# Single-Phase-Energy-Meter_v1_4-rev1.net
KiCad netlist of a schematic drawn in EAGLE
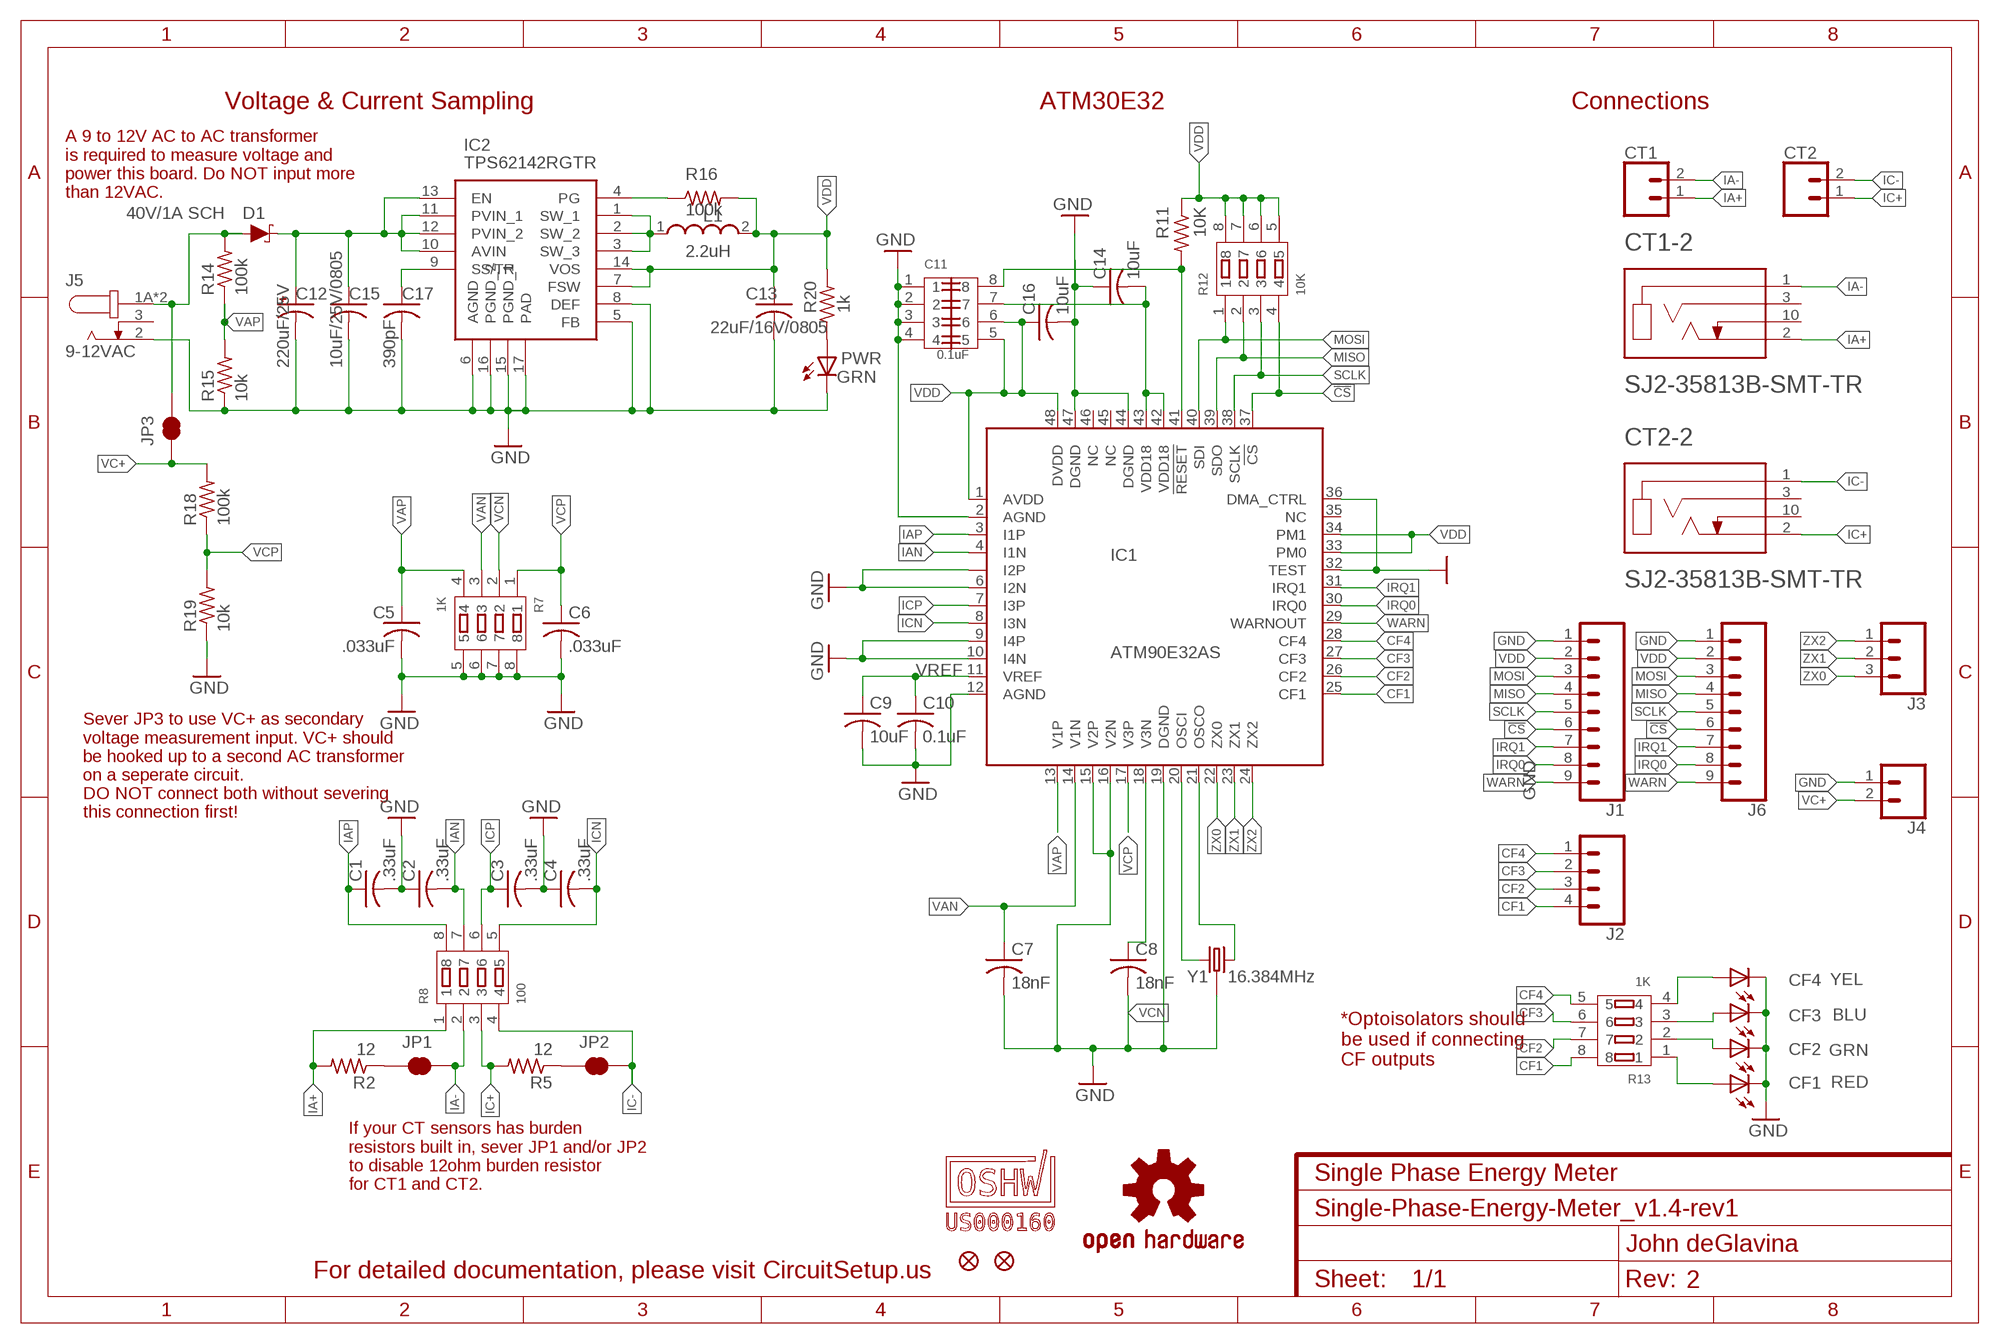
[diagram p0: schematic, sheet 1]

(export (version "E")
  (design (tool "Eeschema 10.0.6"))
  (components
    (comp (ref "C1")
      (value ".33uF")
      (footprint "eagle-import:C0603")
      (libsource (lib "eagle-import") (part "C-USC0603"))
    )
    (comp (ref "C2")
      (value ".33uF")
      (footprint "eagle-import:C0603")
      (libsource (lib "eagle-import") (part "C-USC0603"))
    )
    (comp (ref "C3")
      (value ".33uF")
      (footprint "eagle-import:C0603")
      (libsource (lib "eagle-import") (part "C-USC0603"))
    )
    (comp (ref "C4")
      (value ".33uF")
      (footprint "eagle-import:C0603")
      (libsource (lib "eagle-import") (part "C-USC0603"))
    )
    (comp (ref "C5")
      (value ".033uF")
      (footprint "eagle-import:C0603")
      (libsource (lib "eagle-import") (part "C-USC0603"))
    )
    (comp (ref "C6")
      (value ".033uF")
      (footprint "eagle-import:C0603")
      (libsource (lib "eagle-import") (part "C-USC0603"))
    )
    (comp (ref "C7")
      (value "18nF")
      (footprint "eagle-import:C0603")
      (libsource (lib "eagle-import") (part "C-USC0603"))
    )
    (comp (ref "C8")
      (value "18nF")
      (footprint "eagle-import:C0603")
      (libsource (lib "eagle-import") (part "C-USC0603"))
    )
    (comp (ref "C9")
      (value "10uF")
      (footprint "eagle-import:C0603")
      (libsource (lib "eagle-import") (part "C-USC0603"))
    )
    (comp (ref "C10")
      (value "0.1uF")
      (footprint "eagle-import:C0603")
      (libsource (lib "eagle-import") (part "C-USC0603"))
    )
    (comp (ref "C11")
      (value "0.1uF")
      (footprint "eagle-import:CAPCAF80P320X160X70-8")
      (libsource (lib "eagle-import") (part "CAP-ARRAY4"))
    )
    (comp (ref "C12")
      (value "220uF/25V")
      (footprint "eagle-import:153CLV-0605")
      (libsource (lib "eagle-import") (part "CPOL-US153CLV-0605"))
    )
    (comp (ref "C13")
      (value "22uF/16V/0805")
      (footprint "eagle-import:C0805")
      (libsource (lib "eagle-import") (part "C-USC0805"))
    )
    (comp (ref "C14")
      (value "10uF")
      (footprint "eagle-import:C0603")
      (libsource (lib "eagle-import") (part "C-USC0603"))
    )
    (comp (ref "C15")
      (value "10uF/25V/0805")
      (footprint "eagle-import:C0805")
      (libsource (lib "eagle-import") (part "C-USC0805"))
    )
    (comp (ref "C16")
      (value "10uF")
      (footprint "eagle-import:C0603")
      (libsource (lib "eagle-import") (part "C-USC0603"))
    )
    (comp (ref "C17")
      (value "390pF")
      (footprint "eagle-import:C0603")
      (libsource (lib "eagle-import") (part "C-USC0603"))
    )
    (comp (ref "CF1")
      (value "RED")
      (footprint "eagle-import:CHIP-LED0603")
      (libsource (lib "eagle-import") (part "LEDCHIP-LED0603"))
    )
    (comp (ref "CF2")
      (value "GRN")
      (footprint "eagle-import:CHIP-LED0603")
      (libsource (lib "eagle-import") (part "LEDCHIP-LED0603"))
    )
    (comp (ref "CF3")
      (value "BLU")
      (footprint "eagle-import:CHIP-LED0603")
      (libsource (lib "eagle-import") (part "LEDCHIP-LED0603"))
    )
    (comp (ref "CF4")
      (value "YEL")
      (footprint "eagle-import:CHIP-LED0603")
      (libsource (lib "eagle-import") (part "LEDCHIP-LED0603"))
    )
    (comp (ref "CT1")
      (value "CONN_023.5MM")
      (footprint "eagle-import:SCREWTERMINAL-3.5MM-2")
      (libsource (lib "eagle-import") (part "CONN_023.5MM"))
    )
    (comp (ref "CT1-2")
      (value "SJ2-35813B-SMT-TR")
      (footprint "eagle-import:CUI_SJ2-35813B-SMT-TR")
      (fields (field (name "MANUFACTURER") "CUI"))
      (libsource (lib "eagle-import") (part "SJ2-35813B-SMT-TR"))
    )
    (comp (ref "CT2")
      (value "CONN_023.5MM")
      (footprint "eagle-import:SCREWTERMINAL-3.5MM-2")
      (libsource (lib "eagle-import") (part "CONN_023.5MM"))
    )
    (comp (ref "CT2-2")
      (value "SJ2-35813B-SMT-TR")
      (footprint "eagle-import:CUI_SJ2-35813B-SMT-TR")
      (fields (field (name "MANUFACTURER") "CUI"))
      (libsource (lib "eagle-import") (part "SJ2-35813B-SMT-TR"))
    )
    (comp (ref "D1")
      (value "40V/1A SCH")
      (footprint "eagle-import:SMA-DIODE")
      (libsource (lib "eagle-import") (part "DIODE-SCHOTTKY-SS14"))
    )
    (comp (ref "FD1")
      (value "FIDUCIALUFIDUCIAL")
      (footprint "eagle-import:FIDUCIAL-MICRO")
      (libsource (lib "eagle-import") (part "FIDUCIALUFIDUCIAL"))
    )
    (comp (ref "FD2")
      (value "FIDUCIALUFIDUCIAL")
      (footprint "eagle-import:FIDUCIAL-MICRO")
      (libsource (lib "eagle-import") (part "FIDUCIALUFIDUCIAL"))
    )
    (comp (ref "IC1")
      (value "ATM90E32AS")
      (footprint "eagle-import:QFP50P900X900X120-48N")
      (fields (field (name "SPICEPREFIX") "X"))
      (libsource (lib "eagle-import") (part "ATM90E36"))
    )
    (comp (ref "IC2")
      (value "TPS62142RGTR")
      (footprint "eagle-import:QFN50P300X300X100-17N")
      (fields (field (name "MOUSER_PART_NUMBER") "595-TPS62142RGTR"))
      (libsource (lib "eagle-import") (part "TPS62142RGTR"))
    )
    (comp (ref "J1")
      (value "CONN_09")
      (footprint "eagle-import:1X09")
      (libsource (lib "eagle-import") (part "CONN_09"))
    )
    (comp (ref "J2")
      (value "CONN_04")
      (footprint "eagle-import:1X04")
      (libsource (lib "eagle-import") (part "CONN_04"))
    )
    (comp (ref "J3")
      (value "CONN_03")
      (footprint "eagle-import:1X03")
      (libsource (lib "eagle-import") (part "CONN_03"))
    )
    (comp (ref "J4")
      (value "CONN_02")
      (footprint "eagle-import:1X02")
      (libsource (lib "eagle-import") (part "CONN_02"))
    )
    (comp (ref "J5")
      (value "9-12VAC")
      (footprint "eagle-import:CUI_PJ-002AH-SMT-TR")
      (fields (field (name "MF") "CUI") (field (name "MP") "PJ-002AH-SMT-TR"))
      (libsource (lib "eagle-import") (part "PJ-002AH-SMT-TR"))
    )
    (comp (ref "J6")
      (value "CONN_09")
      (footprint "eagle-import:1X09")
      (libsource (lib "eagle-import") (part "CONN_09"))
    )
    (comp (ref "JP1")
      (value "JUMPER-SMT_2_NC_TRACE_SILK")
      (footprint "eagle-import:SMT-JUMPER_2_NC_TRACE_SILK")
      (libsource (lib "eagle-import") (part "JUMPER-SMT_2_NC_TRACE_SILK"))
    )
    (comp (ref "JP2")
      (value "JUMPER-SMT_2_NC_TRACE_SILK")
      (footprint "eagle-import:SMT-JUMPER_2_NC_TRACE_SILK")
      (libsource (lib "eagle-import") (part "JUMPER-SMT_2_NC_TRACE_SILK"))
    )
    (comp (ref "JP3")
      (value "JUMPER-SMT_2_NC_TRACE_SILK")
      (footprint "eagle-import:SMT-JUMPER_2_NC_TRACE_SILK")
      (libsource (lib "eagle-import") (part "JUMPER-SMT_2_NC_TRACE_SILK"))
    )
    (comp (ref "L1")
      (value "2.2uH")
      (footprint "eagle-import:INDPM4042X200N")
      (fields (field (name "ARROW_PART_NUMBER") "PA4332.222NLT"))
      (libsource (lib "eagle-import") (part "PA4332.222NLT"))
    )
    (comp (ref "LOGO1")
      (value "OSHW-LOGOS")
      (footprint "eagle-import:OSHW-LOGO-S")
      (libsource (lib "eagle-import") (part "OSHW-LOGOS"))
    )
    (comp (ref "PWR")
      (value "GRN")
      (footprint "eagle-import:CHIP-LED0603")
      (libsource (lib "eagle-import") (part "LEDCHIP-LED0603"))
    )
    (comp (ref "R2")
      (value "12")
      (footprint "eagle-import:R0603")
      (libsource (lib "eagle-import") (part "R-US_R0603"))
    )
    (comp (ref "R5")
      (value "12")
      (footprint "eagle-import:R0603")
      (libsource (lib "eagle-import") (part "R-US_R0603"))
    )
    (comp (ref "R7")
      (value "1K")
      (footprint "eagle-import:RA1206-8")
      (fields (field (name "MPN") "Chip-Array-Series-1%"))
      (libsource (lib "eagle-import") (part "SMD-RES-ARRAY-1K-4R(RA1206-8)"))
    )
    (comp (ref "R8")
      (value "100")
      (footprint "eagle-import:RA1206-8")
      (fields (field (name "MPN") "Chip-Array-Series-1%"))
      (libsource (lib "eagle-import") (part "SMD-RES-ARRAY-1K-4R(RA1206-8)"))
    )
    (comp (ref "R11")
      (value "10K")
      (footprint "eagle-import:R0603")
      (libsource (lib "eagle-import") (part "R-US_R0603"))
    )
    (comp (ref "R12")
      (value "10K")
      (footprint "eagle-import:RA1206-8")
      (fields (field (name "MPN") "Chip-Array-Series-1%"))
      (libsource (lib "eagle-import") (part "SMD-RES-ARRAY-1K-4R(RA1206-8)"))
    )
    (comp (ref "R13")
      (value "1K")
      (footprint "eagle-import:RA1206-8")
      (fields (field (name "MPN") "Chip-Array-Series-1%"))
      (libsource (lib "eagle-import") (part "SMD-RES-ARRAY-1K-4R(RA1206-8)"))
    )
    (comp (ref "R14")
      (value "100k")
      (footprint "eagle-import:R0603")
      (libsource (lib "eagle-import") (part "R-US_R0603"))
    )
    (comp (ref "R15")
      (value "10k")
      (footprint "eagle-import:R0603")
      (libsource (lib "eagle-import") (part "R-US_R0603"))
    )
    (comp (ref "R16")
      (value "100k")
      (footprint "eagle-import:R0603")
      (libsource (lib "eagle-import") (part "R-US_R0603"))
    )
    (comp (ref "R18")
      (value "100k")
      (footprint "eagle-import:R0603")
      (libsource (lib "eagle-import") (part "R-US_R0603"))
    )
    (comp (ref "R19")
      (value "10k")
      (footprint "eagle-import:R0603")
      (libsource (lib "eagle-import") (part "R-US_R0603"))
    )
    (comp (ref "R20")
      (value "1k")
      (footprint "eagle-import:R0603")
      (libsource (lib "eagle-import") (part "R-US_R0603"))
    )
    (comp (ref "U$1")
      (value "CS_OSHW_LOGOS")
      (footprint "eagle-import:OSHW160")
      (libsource (lib "eagle-import") (part "CS_OSHW_LOGOS"))
    )
    (comp (ref "Y1")
      (value "16.384MHz")
      (footprint "eagle-import:CRYSTAL-SMD-3.2X2.5MM")
      (libsource (lib "eagle-import") (part "CRYSTAL-GROUNDEDSMD-3.2X2.5"))
    )
  )
  (nets
    (net (code "1") (name "/VREF") (class "Default")
      (node (ref "C10") (pin "1") (pinfunction "1_1") (pintype "passive"))
      (node (ref "C9") (pin "1") (pinfunction "1_1") (pintype "passive"))
      (node (ref "IC1") (pin "11") (pinfunction "VREF_11") (pintype "bidirectional"))
    )
    (net (code "2") (name "/~{CS}") (class "Default")
      (node (ref "IC1") (pin "37") (pinfunction "~{CS}_37") (pintype "input"))
      (node (ref "J1") (pin "6") (pinfunction "6_6") (pintype "passive"))
      (node (ref "J6") (pin "6") (pinfunction "6_6") (pintype "passive"))
      (node (ref "R12") (pin "4") (pinfunction "4_4") (pintype "bidirectional"))
    )
    (net (code "3") (name "CF1") (class "Default")
      (node (ref "IC1") (pin "25") (pinfunction "CF1_25") (pintype "output"))
      (node (ref "J2") (pin "4") (pinfunction "4_4") (pintype "passive"))
      (node (ref "R13") (pin "8") (pinfunction "8_8") (pintype "bidirectional"))
    )
    (net (code "4") (name "CF2") (class "Default")
      (node (ref "IC1") (pin "26") (pinfunction "CF2_26") (pintype "output"))
      (node (ref "J2") (pin "3") (pinfunction "3_3") (pintype "passive"))
      (node (ref "R13") (pin "7") (pinfunction "7_7") (pintype "bidirectional"))
    )
    (net (code "5") (name "CF3") (class "Default")
      (node (ref "IC1") (pin "27") (pinfunction "CF3_27") (pintype "output"))
      (node (ref "J2") (pin "2") (pinfunction "2_2") (pintype "passive"))
      (node (ref "R13") (pin "6") (pinfunction "6_6") (pintype "bidirectional"))
    )
    (net (code "6") (name "CF4") (class "Default")
      (node (ref "IC1") (pin "28") (pinfunction "CF4_28") (pintype "output"))
      (node (ref "J2") (pin "1") (pinfunction "1_1") (pintype "passive"))
      (node (ref "R13") (pin "5") (pinfunction "5_5") (pintype "bidirectional"))
    )
    (net (code "7") (name "GND") (class "Default")
      (node (ref "C1") (pin "2") (pinfunction "2_2") (pintype "passive"))
      (node (ref "C10") (pin "2") (pinfunction "2_2") (pintype "passive"))
      (node (ref "C11") (pin "1") (pinfunction "1_1") (pintype "bidirectional"))
      (node (ref "C11") (pin "2") (pinfunction "2_2") (pintype "bidirectional"))
      (node (ref "C11") (pin "3") (pinfunction "3_3") (pintype "bidirectional"))
      (node (ref "C11") (pin "4") (pinfunction "4_4") (pintype "bidirectional"))
      (node (ref "C12") (pin "-") (pinfunction "-_-") (pintype "passive"))
      (node (ref "C13") (pin "2") (pinfunction "2_2") (pintype "passive"))
      (node (ref "C14") (pin "1") (pinfunction "1_1") (pintype "passive"))
      (node (ref "C15") (pin "2") (pinfunction "2_2") (pintype "passive"))
      (node (ref "C16") (pin "2") (pinfunction "2_2") (pintype "passive"))
      (node (ref "C17") (pin "2") (pinfunction "2_2") (pintype "passive"))
      (node (ref "C2") (pin "1") (pinfunction "1_1") (pintype "passive"))
      (node (ref "C3") (pin "2") (pinfunction "2_2") (pintype "passive"))
      (node (ref "C4") (pin "1") (pinfunction "1_1") (pintype "passive"))
      (node (ref "C5") (pin "2") (pinfunction "2_2") (pintype "passive"))
      (node (ref "C6") (pin "2") (pinfunction "2_2") (pintype "passive"))
      (node (ref "C7") (pin "2") (pinfunction "2_2") (pintype "passive"))
      (node (ref "C8") (pin "2") (pinfunction "2_2") (pintype "passive"))
      (node (ref "C9") (pin "2") (pinfunction "2_2") (pintype "passive"))
      (node (ref "CF1") (pin "C") (pinfunction "C_C") (pintype "passive"))
      (node (ref "CF2") (pin "C") (pinfunction "C_C") (pintype "passive"))
      (node (ref "CF3") (pin "C") (pinfunction "C_C") (pintype "passive"))
      (node (ref "CF4") (pin "C") (pinfunction "C_C") (pintype "passive"))
      (node (ref "IC1") (pin "10") (pinfunction "I4N_10") (pintype "input"))
      (node (ref "IC1") (pin "12") (pinfunction "AGND_12") (pintype "power_in"))
      (node (ref "IC1") (pin "15") (pinfunction "V2P_15") (pintype "input"))
      (node (ref "IC1") (pin "16") (pinfunction "V2N_16") (pintype "input"))
      (node (ref "IC1") (pin "19") (pinfunction "DGND_19") (pintype "power_in"))
      (node (ref "IC1") (pin "2") (pinfunction "AGND_2") (pintype "power_in"))
      (node (ref "IC1") (pin "32") (pinfunction "TEST_32") (pintype "power_in"))
      (node (ref "IC1") (pin "36") (pinfunction "DMA_CTRL_36") (pintype "input"))
      (node (ref "IC1") (pin "44") (pinfunction "DGND_44") (pintype "power_in"))
      (node (ref "IC1") (pin "47") (pinfunction "DGND_47") (pintype "power_in"))
      (node (ref "IC1") (pin "5") (pinfunction "I2P_5") (pintype "input"))
      (node (ref "IC1") (pin "6") (pinfunction "I2N_6") (pintype "input"))
      (node (ref "IC1") (pin "9") (pinfunction "I4P_9") (pintype "input"))
      (node (ref "IC2") (pin "15") (pinfunction "PGND_1_15") (pintype "bidirectional"))
      (node (ref "IC2") (pin "16") (pinfunction "PGND_2_16") (pintype "bidirectional"))
      (node (ref "IC2") (pin "17") (pinfunction "PAD_17") (pintype "bidirectional"))
      (node (ref "IC2") (pin "5") (pinfunction "FB_5") (pintype "bidirectional"))
      (node (ref "IC2") (pin "6") (pinfunction "AGND_6") (pintype "bidirectional"))
      (node (ref "IC2") (pin "8") (pinfunction "DEF_8") (pintype "bidirectional"))
      (node (ref "J1") (pin "1") (pinfunction "1_1") (pintype "passive"))
      (node (ref "J4") (pin "1") (pinfunction "1_1") (pintype "passive"))
      (node (ref "J5") (pin "2") (pinfunction "2_2") (pintype "passive"))
      (node (ref "J6") (pin "1") (pinfunction "1_1") (pintype "passive"))
      (node (ref "PWR") (pin "C") (pinfunction "C_C") (pintype "passive"))
      (node (ref "R15") (pin "1") (pinfunction "1_1") (pintype "passive"))
      (node (ref "R19") (pin "1") (pinfunction "1_1") (pintype "passive"))
      (node (ref "R7") (pin "5") (pinfunction "5_5") (pintype "bidirectional"))
      (node (ref "R7") (pin "6") (pinfunction "6_6") (pintype "bidirectional"))
      (node (ref "R7") (pin "7") (pinfunction "7_7") (pintype "bidirectional"))
      (node (ref "R7") (pin "8") (pinfunction "8_8") (pintype "bidirectional"))
      (node (ref "Y1") (pin "2") (pinfunction "3_2") (pintype "passive"))
      (node (ref "Y1") (pin "4") (pinfunction "3_4") (pintype "passive"))
    )
    (net (code "8") (name "IA+") (class "Default")
      (node (ref "CT1") (pin "1") (pinfunction "1_1") (pintype "passive"))
      (node (ref "CT1-2") (pin "2") (pinfunction "TIP_2") (pintype "passive"))
      (node (ref "R2") (pin "2") (pinfunction "2_2") (pintype "passive"))
      (node (ref "R8") (pin "1") (pinfunction "1_1") (pintype "bidirectional"))
    )
    (net (code "9") (name "IA-") (class "Default")
      (node (ref "CT1") (pin "2") (pinfunction "2_2") (pintype "passive"))
      (node (ref "CT1-2") (pin "1") (pinfunction "SLEEVE_1") (pintype "passive"))
      (node (ref "JP1") (pin "2") (pinfunction "2_2") (pintype "passive"))
      (node (ref "R8") (pin "2") (pinfunction "2_2") (pintype "bidirectional"))
    )
    (net (code "10") (name "IAN") (class "Default")
      (node (ref "C2") (pin "2") (pinfunction "2_2") (pintype "passive"))
      (node (ref "IC1") (pin "4") (pinfunction "I1N_4") (pintype "input"))
      (node (ref "R8") (pin "7") (pinfunction "7_7") (pintype "bidirectional"))
    )
    (net (code "11") (name "IAP") (class "Default")
      (node (ref "C1") (pin "1") (pinfunction "1_1") (pintype "passive"))
      (node (ref "IC1") (pin "3") (pinfunction "I1P_3") (pintype "input"))
      (node (ref "R8") (pin "8") (pinfunction "8_8") (pintype "bidirectional"))
    )
    (net (code "12") (name "IC+") (class "Default")
      (node (ref "CT2") (pin "1") (pinfunction "1_1") (pintype "passive"))
      (node (ref "CT2-2") (pin "2") (pinfunction "TIP_2") (pintype "passive"))
      (node (ref "R5") (pin "2") (pinfunction "2_2") (pintype "passive"))
      (node (ref "R8") (pin "3") (pinfunction "3_3") (pintype "bidirectional"))
    )
    (net (code "13") (name "IC-") (class "Default")
      (node (ref "CT2") (pin "2") (pinfunction "2_2") (pintype "passive"))
      (node (ref "CT2-2") (pin "1") (pinfunction "SLEEVE_1") (pintype "passive"))
      (node (ref "JP2") (pin "2") (pinfunction "2_2") (pintype "passive"))
      (node (ref "R8") (pin "4") (pinfunction "4_4") (pintype "bidirectional"))
    )
    (net (code "14") (name "ICN") (class "Default")
      (node (ref "C4") (pin "2") (pinfunction "2_2") (pintype "passive"))
      (node (ref "IC1") (pin "8") (pinfunction "I3N_8") (pintype "input"))
      (node (ref "R8") (pin "5") (pinfunction "5_5") (pintype "bidirectional"))
    )
    (net (code "15") (name "ICP") (class "Default")
      (node (ref "C3") (pin "1") (pinfunction "1_1") (pintype "passive"))
      (node (ref "IC1") (pin "7") (pinfunction "I3P_7") (pintype "input"))
      (node (ref "R8") (pin "6") (pinfunction "6_6") (pintype "bidirectional"))
    )
    (net (code "16") (name "IRQ0") (class "Default")
      (node (ref "IC1") (pin "30") (pinfunction "IRQ0_30") (pintype "output"))
      (node (ref "J1") (pin "8") (pinfunction "8_8") (pintype "passive"))
      (node (ref "J6") (pin "8") (pinfunction "8_8") (pintype "passive"))
    )
    (net (code "17") (name "IRQ1") (class "Default")
      (node (ref "IC1") (pin "31") (pinfunction "IRQ1_31") (pintype "output"))
      (node (ref "J1") (pin "7") (pinfunction "7_7") (pintype "passive"))
      (node (ref "J6") (pin "7") (pinfunction "7_7") (pintype "passive"))
    )
    (net (code "18") (name "MISO") (class "Default")
      (node (ref "IC1") (pin "39") (pinfunction "SDO_39") (pintype "output"))
      (node (ref "J1") (pin "4") (pinfunction "4_4") (pintype "passive"))
      (node (ref "J6") (pin "4") (pinfunction "4_4") (pintype "passive"))
      (node (ref "R12") (pin "2") (pinfunction "2_2") (pintype "bidirectional"))
    )
    (net (code "19") (name "MOSI") (class "Default")
      (node (ref "IC1") (pin "40") (pinfunction "SDI_40") (pintype "input"))
      (node (ref "J1") (pin "3") (pinfunction "3_3") (pintype "passive"))
      (node (ref "J6") (pin "3") (pinfunction "3_3") (pintype "passive"))
      (node (ref "R12") (pin "1") (pinfunction "1_1") (pintype "bidirectional"))
    )
    (net (code "20") (name "Net-(C11-Pad7)") (class "Default")
      (node (ref "C11") (pin "7") (pinfunction "7_7") (pintype "bidirectional"))
      (node (ref "C14") (pin "2") (pinfunction "2_2") (pintype "passive"))
      (node (ref "IC1") (pin "42") (pinfunction "VDD18_42") (pintype "power_in"))
      (node (ref "IC1") (pin "43") (pinfunction "VDD18_43") (pintype "power_in"))
    )
    (net (code "21") (name "Net-(CF1-PadA)") (class "Default")
      (node (ref "CF1") (pin "A") (pinfunction "A_A") (pintype "passive"))
      (node (ref "R13") (pin "1") (pinfunction "1_1") (pintype "bidirectional"))
    )
    (net (code "22") (name "Net-(CF2-PadA)") (class "Default")
      (node (ref "CF2") (pin "A") (pinfunction "A_A") (pintype "passive"))
      (node (ref "R13") (pin "2") (pinfunction "2_2") (pintype "bidirectional"))
    )
    (net (code "23") (name "Net-(CF3-PadA)") (class "Default")
      (node (ref "CF3") (pin "A") (pinfunction "A_A") (pintype "passive"))
      (node (ref "R13") (pin "3") (pinfunction "3_3") (pintype "bidirectional"))
    )
    (net (code "24") (name "Net-(CF4-PadA)") (class "Default")
      (node (ref "CF4") (pin "A") (pinfunction "A_A") (pintype "passive"))
      (node (ref "R13") (pin "4") (pinfunction "4_4") (pintype "bidirectional"))
    )
    (net (code "25") (name "Net-(D1-PadA)") (class "Default")
      (node (ref "D1") (pin "A") (pinfunction "A_A") (pintype "passive"))
      (node (ref "J5") (pin "1A") (pinfunction "1_1A") (pintype "passive"))
      (node (ref "J5") (pin "1B") (pinfunction "1_1B") (pintype "passive"))
      (node (ref "JP3") (pin "2") (pinfunction "2_2") (pintype "passive"))
      (node (ref "R14") (pin "2") (pinfunction "2_2") (pintype "passive"))
    )
    (net (code "26") (name "Net-(IC1-OSCI)") (class "Default")
      (node (ref "IC1") (pin "20") (pinfunction "OSCI_20") (pintype "input"))
      (node (ref "Y1") (pin "1") (pinfunction "1_1") (pintype "passive"))
    )
    (net (code "27") (name "Net-(IC1-OSCO)") (class "Default")
      (node (ref "IC1") (pin "21") (pinfunction "OSCO_21") (pintype "output"))
      (node (ref "Y1") (pin "3") (pinfunction "2_3") (pintype "passive"))
    )
    (net (code "28") (name "Net-(IC1-~{RESET})") (class "Default")
      (node (ref "C11") (pin "8") (pinfunction "8_8") (pintype "bidirectional"))
      (node (ref "IC1") (pin "41") (pinfunction "~{RESET}_41") (pintype "input"))
      (node (ref "R11") (pin "2") (pinfunction "2_2") (pintype "passive"))
    )
    (net (code "29") (name "Net-(IC2-AVIN)") (class "Default")
      (node (ref "C12") (pin "+") (pinfunction "+_+") (pintype "passive"))
      (node (ref "C15") (pin "1") (pinfunction "1_1") (pintype "passive"))
      (node (ref "D1") (pin "C") (pinfunction "C_C") (pintype "passive"))
      (node (ref "IC2") (pin "10") (pinfunction "AVIN_10") (pintype "bidirectional"))
      (node (ref "IC2") (pin "11") (pinfunction "PVIN_1_11") (pintype "bidirectional"))
      (node (ref "IC2") (pin "12") (pinfunction "PVIN_2_12") (pintype "bidirectional"))
      (node (ref "IC2") (pin "13") (pinfunction "EN_13") (pintype "bidirectional"))
    )
    (net (code "30") (name "Net-(IC2-PG)") (class "Default")
      (node (ref "IC2") (pin "4") (pinfunction "PG_4") (pintype "bidirectional"))
      (node (ref "R16") (pin "1") (pinfunction "1_1") (pintype "passive"))
    )
    (net (code "31") (name "Net-(IC2-SS{slash}TR)") (class "Default")
      (node (ref "C17") (pin "1") (pinfunction "1_1") (pintype "passive"))
      (node (ref "IC2") (pin "9") (pinfunction "SS/TR_9") (pintype "bidirectional"))
    )
    (net (code "32") (name "Net-(IC2-SW_1)") (class "Default")
      (node (ref "IC2") (pin "1") (pinfunction "SW_1_1") (pintype "bidirectional"))
      (node (ref "IC2") (pin "2") (pinfunction "SW_2_2") (pintype "bidirectional"))
      (node (ref "IC2") (pin "3") (pinfunction "SW_3_3") (pintype "bidirectional"))
      (node (ref "L1") (pin "1") (pinfunction "1_1") (pintype "bidirectional"))
    )
    (net (code "33") (name "Net-(JP1-Pad1)") (class "Default")
      (node (ref "JP1") (pin "1") (pinfunction "1_1") (pintype "passive"))
      (node (ref "R2") (pin "1") (pinfunction "1_1") (pintype "passive"))
    )
    (net (code "34") (name "Net-(JP2-Pad1)") (class "Default")
      (node (ref "JP2") (pin "1") (pinfunction "1_1") (pintype "passive"))
      (node (ref "R5") (pin "1") (pinfunction "1_1") (pintype "passive"))
    )
    (net (code "35") (name "Net-(PWR-PadA)") (class "Default")
      (node (ref "PWR") (pin "A") (pinfunction "A_A") (pintype "passive"))
      (node (ref "R20") (pin "1") (pinfunction "1_1") (pintype "passive"))
    )
    (net (code "36") (name "SCLK") (class "Default")
      (node (ref "IC1") (pin "38") (pinfunction "SCLK_38") (pintype "input"))
      (node (ref "J1") (pin "5") (pinfunction "5_5") (pintype "passive"))
      (node (ref "J6") (pin "5") (pinfunction "5_5") (pintype "passive"))
      (node (ref "R12") (pin "3") (pinfunction "3_3") (pintype "bidirectional"))
    )
    (net (code "37") (name "VAN") (class "Default")
      (node (ref "C7") (pin "1") (pinfunction "1_1") (pintype "passive"))
      (node (ref "IC1") (pin "14") (pinfunction "V1N_14") (pintype "input"))
      (node (ref "R7") (pin "3") (pinfunction "3_3") (pintype "bidirectional"))
    )
    (net (code "38") (name "VAP") (class "Default")
      (node (ref "C5") (pin "1") (pinfunction "1_1") (pintype "passive"))
      (node (ref "IC1") (pin "13") (pinfunction "V1P_13") (pintype "input"))
      (node (ref "R14") (pin "1") (pinfunction "1_1") (pintype "passive"))
      (node (ref "R15") (pin "2") (pinfunction "2_2") (pintype "passive"))
      (node (ref "R7") (pin "4") (pinfunction "4_4") (pintype "bidirectional"))
    )
    (net (code "39") (name "VC+") (class "Default")
      (node (ref "J4") (pin "2") (pinfunction "2_2") (pintype "passive"))
      (node (ref "JP3") (pin "1") (pinfunction "1_1") (pintype "passive"))
      (node (ref "R18") (pin "2") (pinfunction "2_2") (pintype "passive"))
    )
    (net (code "40") (name "VCN") (class "Default")
      (node (ref "C8") (pin "1") (pinfunction "1_1") (pintype "passive"))
      (node (ref "IC1") (pin "18") (pinfunction "V3N_18") (pintype "input"))
      (node (ref "R7") (pin "2") (pinfunction "2_2") (pintype "bidirectional"))
    )
    (net (code "41") (name "VCP") (class "Default")
      (node (ref "C6") (pin "1") (pinfunction "1_1") (pintype "passive"))
      (node (ref "IC1") (pin "17") (pinfunction "V3P_17") (pintype "input"))
      (node (ref "R18") (pin "1") (pinfunction "1_1") (pintype "passive"))
      (node (ref "R19") (pin "2") (pinfunction "2_2") (pintype "passive"))
      (node (ref "R7") (pin "1") (pinfunction "1_1") (pintype "bidirectional"))
    )
    (net (code "42") (name "VDD") (class "Default")
      (node (ref "C11") (pin "5") (pinfunction "5_5") (pintype "bidirectional"))
      (node (ref "C11") (pin "6") (pinfunction "6_6") (pintype "bidirectional"))
      (node (ref "C13") (pin "1") (pinfunction "1_1") (pintype "passive"))
      (node (ref "C16") (pin "1") (pinfunction "1_1") (pintype "passive"))
      (node (ref "IC1") (pin "1") (pinfunction "AVDD_1") (pintype "power_in"))
      (node (ref "IC1") (pin "33") (pinfunction "PM0_33") (pintype "input"))
      (node (ref "IC1") (pin "34") (pinfunction "PM1_34") (pintype "input"))
      (node (ref "IC1") (pin "48") (pinfunction "DVDD_48") (pintype "power_in"))
      (node (ref "IC2") (pin "14") (pinfunction "VOS_14") (pintype "bidirectional"))
      (node (ref "IC2") (pin "7") (pinfunction "FSW_7") (pintype "bidirectional"))
      (node (ref "J1") (pin "2") (pinfunction "2_2") (pintype "passive"))
      (node (ref "J6") (pin "2") (pinfunction "2_2") (pintype "passive"))
      (node (ref "L1") (pin "2") (pinfunction "2_2") (pintype "bidirectional"))
      (node (ref "R11") (pin "1") (pinfunction "1_1") (pintype "passive"))
      (node (ref "R12") (pin "5") (pinfunction "5_5") (pintype "bidirectional"))
      (node (ref "R12") (pin "6") (pinfunction "6_6") (pintype "bidirectional"))
      (node (ref "R12") (pin "7") (pinfunction "7_7") (pintype "bidirectional"))
      (node (ref "R12") (pin "8") (pinfunction "8_8") (pintype "bidirectional"))
      (node (ref "R16") (pin "2") (pinfunction "2_2") (pintype "passive"))
      (node (ref "R20") (pin "2") (pinfunction "2_2") (pintype "passive"))
    )
    (net (code "43") (name "WARN") (class "Default")
      (node (ref "IC1") (pin "29") (pinfunction "WARNOUT_29") (pintype "output"))
      (node (ref "J1") (pin "9") (pinfunction "9_9") (pintype "passive"))
      (node (ref "J6") (pin "9") (pinfunction "9_9") (pintype "passive"))
    )
    (net (code "44") (name "ZX0") (class "Default")
      (node (ref "IC1") (pin "22") (pinfunction "ZX0_22") (pintype "output"))
      (node (ref "J3") (pin "3") (pinfunction "3_3") (pintype "passive"))
    )
    (net (code "45") (name "ZX1") (class "Default")
      (node (ref "IC1") (pin "23") (pinfunction "ZX1_23") (pintype "output"))
      (node (ref "J3") (pin "2") (pinfunction "2_2") (pintype "passive"))
    )
    (net (code "46") (name "ZX2") (class "Default")
      (node (ref "IC1") (pin "24") (pinfunction "ZX2_24") (pintype "output"))
      (node (ref "J3") (pin "1") (pinfunction "1_1") (pintype "passive"))
    )
    (net (code "47") (name "unconnected-(CT1-2-RING-Pad3)") (class "Default")
      (node (ref "CT1-2") (pin "3") (pinfunction "RING_3") (pintype "passive"))
    )
    (net (code "48") (name "unconnected-(CT1-2-TIP_SWITCH-Pad10)") (class "Default")
      (node (ref "CT1-2") (pin "10") (pinfunction "TIP_SWITCH_10") (pintype "passive"))
    )
    (net (code "49") (name "unconnected-(CT2-2-RING-Pad3)") (class "Default")
      (node (ref "CT2-2") (pin "3") (pinfunction "RING_3") (pintype "passive"))
    )
    (net (code "50") (name "unconnected-(CT2-2-TIP_SWITCH-Pad10)") (class "Default")
      (node (ref "CT2-2") (pin "10") (pinfunction "TIP_SWITCH_10") (pintype "passive"))
    )
    (net (code "51") (name "unconnected-(IC1-NC-Pad35)") (class "Default")
      (node (ref "IC1") (pin "35") (pinfunction "NC_35") (pintype "no_connect"))
    )
    (net (code "52") (name "unconnected-(IC1-NC-Pad45)") (class "Default")
      (node (ref "IC1") (pin "45") (pinfunction "NC_45") (pintype "no_connect"))
    )
    (net (code "53") (name "unconnected-(IC1-NC-Pad46)") (class "Default")
      (node (ref "IC1") (pin "46") (pinfunction "NC_46") (pintype "no_connect"))
    )
    (net (code "54") (name "unconnected-(J5-Pad3)") (class "Default")
      (node (ref "J5") (pin "3") (pinfunction "3_3") (pintype "passive"))
    )
  )
)
